# Filter.net
KiCad netlist of a schematic drawn in EAGLE
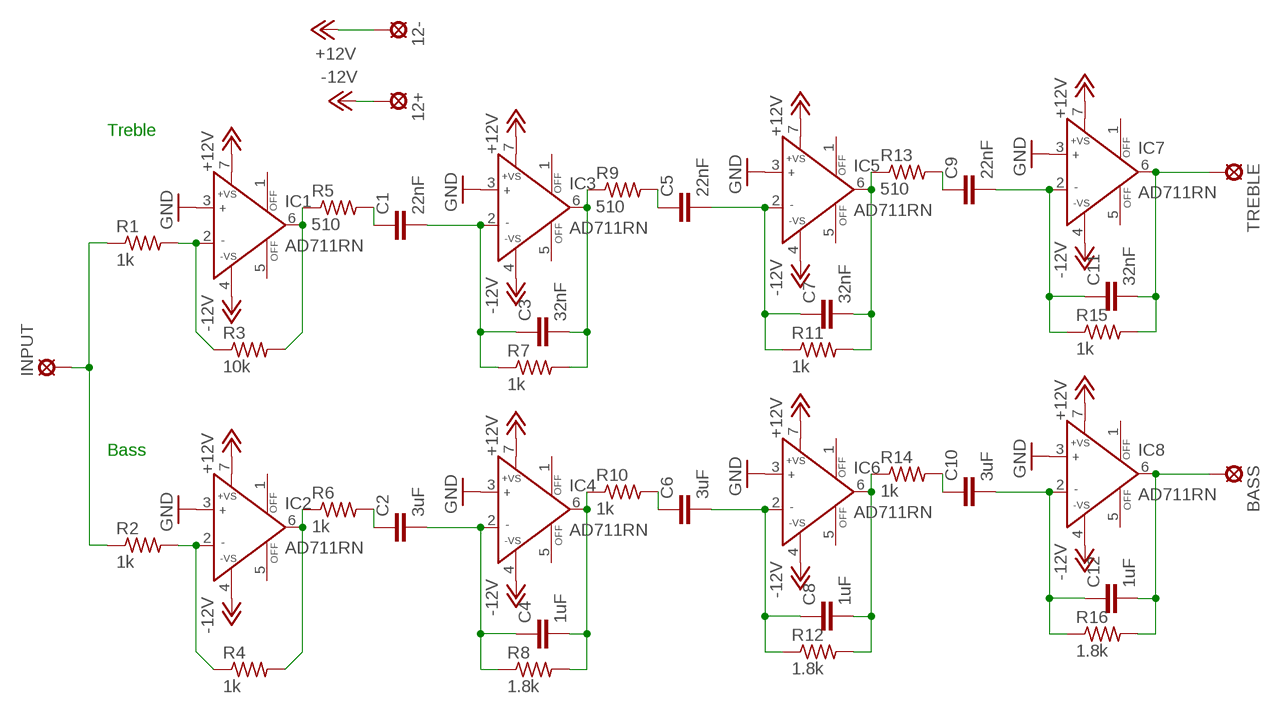
[diagram p0: schematic, sheet 1]

(export (version "E")
  (design (tool "Eeschema 10.0.6"))
  (components
    (comp (ref "12+")
      (value "MCS10B")
      (footprint "eagle-import:MCS10B")
      (libsource (lib "eagle-import") (part "MCS10B"))
    )
    (comp (ref "12-")
      (value "MCS10B")
      (footprint "eagle-import:MCS10B")
      (libsource (lib "eagle-import") (part "MCS10B"))
    )
    (comp (ref "BASS")
      (value "MCS10B")
      (footprint "eagle-import:MCS10B")
      (libsource (lib "eagle-import") (part "MCS10B"))
    )
    (comp (ref "C1")
      (value "22nF")
      (footprint "eagle-import:C0805")
      (fields (field (name "MPN") "UA741CPE4"))
      (libsource (lib "eagle-import") (part "C"))
    )
    (comp (ref "C2")
      (value "3uF")
      (footprint "eagle-import:C0805")
      (fields (field (name "MPN") "TMCP1C335KTRF"))
      (libsource (lib "eagle-import") (part "C"))
    )
    (comp (ref "C3")
      (value "32nF")
      (footprint "eagle-import:C0805")
      (libsource (lib "eagle-import") (part "C"))
    )
    (comp (ref "C4")
      (value "1uF")
      (footprint "eagle-import:C0805")
      (fields (field (name "MPN") "6TPU33MSK"))
      (libsource (lib "eagle-import") (part "C"))
    )
    (comp (ref "C5")
      (value "22nF")
      (footprint "eagle-import:C0805")
      (fields (field (name "MPN") "UA741CPE4"))
      (libsource (lib "eagle-import") (part "C"))
    )
    (comp (ref "C6")
      (value "3uF")
      (footprint "eagle-import:C0805")
      (fields (field (name "MPN") "TMCP1C335KTRF"))
      (libsource (lib "eagle-import") (part "C"))
    )
    (comp (ref "C7")
      (value "32nF")
      (footprint "eagle-import:C0805")
      (libsource (lib "eagle-import") (part "C"))
    )
    (comp (ref "C8")
      (value "1uF")
      (footprint "eagle-import:C0805")
      (fields (field (name "MPN") "6TPU33MSK"))
      (libsource (lib "eagle-import") (part "C"))
    )
    (comp (ref "C9")
      (value "22nF")
      (footprint "eagle-import:C0805")
      (fields (field (name "MPN") "UA741CPE4"))
      (libsource (lib "eagle-import") (part "C"))
    )
    (comp (ref "C10")
      (value "3uF")
      (footprint "eagle-import:C0805")
      (fields (field (name "MPN") "TMCP1C335KTRF"))
      (libsource (lib "eagle-import") (part "C"))
    )
    (comp (ref "C11")
      (value "32nF")
      (footprint "eagle-import:C0805")
      (libsource (lib "eagle-import") (part "C"))
    )
    (comp (ref "C12")
      (value "1uF")
      (footprint "eagle-import:C0805")
      (fields (field (name "MPN") "6TPU33MSK"))
      (libsource (lib "eagle-import") (part "C"))
    )
    (comp (ref "IC1")
      (value "AD711RN")
      (footprint "eagle-import:SO8")
      (fields
        (field (name "MF") "ALTERA CORPORATION")
        (field (name "MPN") "AD711KRZ")
        (field (name "MF_1") "TEXAS INSTRUMENTS")
        (field (name "MPN_1") "UA741CP")
        (field (name "OC_NEWARK") "60K7043")
      )
      (libsource (lib "eagle-import") (part "AD711RN"))
    )
    (comp (ref "IC2")
      (value "AD711RN")
      (footprint "eagle-import:SO8")
      (fields
        (field (name "MF") "ALTERA CORPORATION")
        (field (name "MPN") "AD711KRZ")
        (field (name "MF_1") "TEXAS INSTRUMENTS")
        (field (name "MPN_1") "UA741CP")
        (field (name "OC_NEWARK") "60K7043")
      )
      (libsource (lib "eagle-import") (part "AD711RN"))
    )
    (comp (ref "IC3")
      (value "AD711RN")
      (footprint "eagle-import:SO8")
      (fields
        (field (name "MF") "ALTERA CORPORATION")
        (field (name "MPN") "AD711KRZ")
        (field (name "MF_1") "TEXAS INSTRUMENTS")
        (field (name "MPN_1") "UA741CP")
        (field (name "OC_NEWARK") "60K7043")
      )
      (libsource (lib "eagle-import") (part "AD711RN"))
    )
    (comp (ref "IC4")
      (value "AD711RN")
      (footprint "eagle-import:SO8")
      (fields
        (field (name "MF") "ALTERA CORPORATION")
        (field (name "MPN") "AD711KRZ")
        (field (name "MF_1") "TEXAS INSTRUMENTS")
        (field (name "MPN_1") "UA741CP")
        (field (name "OC_NEWARK") "60K7043")
      )
      (libsource (lib "eagle-import") (part "AD711RN"))
    )
    (comp (ref "IC5")
      (value "AD711RN")
      (footprint "eagle-import:SO8")
      (fields
        (field (name "MF") "ALTERA CORPORATION")
        (field (name "MPN") "AD711KRZ")
        (field (name "MF_1") "TEXAS INSTRUMENTS")
        (field (name "MPN_1") "UA741CP")
        (field (name "OC_NEWARK") "60K7043")
      )
      (libsource (lib "eagle-import") (part "AD711RN"))
    )
    (comp (ref "IC6")
      (value "AD711RN")
      (footprint "eagle-import:SO8")
      (fields
        (field (name "MF") "ALTERA CORPORATION")
        (field (name "MPN") "AD711KRZ")
        (field (name "MF_1") "TEXAS INSTRUMENTS")
        (field (name "MPN_1") "UA741CP")
        (field (name "OC_NEWARK") "60K7043")
      )
      (libsource (lib "eagle-import") (part "AD711RN"))
    )
    (comp (ref "IC7")
      (value "AD711RN")
      (footprint "eagle-import:SO8")
      (fields
        (field (name "MF") "ALTERA CORPORATION")
        (field (name "MPN") "AD711KRZ")
        (field (name "MF_1") "TEXAS INSTRUMENTS")
        (field (name "MPN_1") "UA741CP")
        (field (name "OC_NEWARK") "60K7043")
      )
      (libsource (lib "eagle-import") (part "AD711RN"))
    )
    (comp (ref "IC8")
      (value "AD711RN")
      (footprint "eagle-import:SO8")
      (fields
        (field (name "MF") "ALTERA CORPORATION")
        (field (name "MPN") "AD711KRZ")
        (field (name "MF_1") "TEXAS INSTRUMENTS")
        (field (name "MPN_1") "UA741CP")
        (field (name "OC_NEWARK") "60K7043")
      )
      (libsource (lib "eagle-import") (part "AD711RN"))
    )
    (comp (ref "INPUT")
      (value "MCS10B")
      (footprint "eagle-import:MCS10B")
      (libsource (lib "eagle-import") (part "MCS10B"))
    )
    (comp (ref "R1")
      (value "1k")
      (footprint "eagle-import:R0603")
      (fields (field (name "MPN") "ERJ-3EKF1001V"))
      (libsource (lib "eagle-import") (part "R-US_R0603"))
    )
    (comp (ref "R2")
      (value "1k")
      (footprint "eagle-import:R0603")
      (fields (field (name "MPN") "ERJ-3EKF1001V"))
      (libsource (lib "eagle-import") (part "R-US_R0603"))
    )
    (comp (ref "R3")
      (value "10k")
      (footprint "eagle-import:R0805")
      (fields (field (name "MPN") "MC0603B104K500CT"))
      (libsource (lib "eagle-import") (part "R-US_R0805"))
    )
    (comp (ref "R4")
      (value "1k")
      (footprint "eagle-import:R0603")
      (fields (field (name "MPN") "ERJ-3EKF1001V"))
      (libsource (lib "eagle-import") (part "R-US_R0603"))
    )
    (comp (ref "R5")
      (value "510")
      (footprint "eagle-import:R0805")
      (fields (field (name "MPN") "ERA-6AEB511V"))
      (libsource (lib "eagle-import") (part "R-US_R0805"))
    )
    (comp (ref "R6")
      (value "1k")
      (footprint "eagle-import:R0603")
      (fields (field (name "MPN") "ERJ-3EKF1001V"))
      (libsource (lib "eagle-import") (part "R-US_R0603"))
    )
    (comp (ref "R7")
      (value "1k")
      (footprint "eagle-import:R0603")
      (fields (field (name "MPN") "ERJ-3EKF1001V"))
      (libsource (lib "eagle-import") (part "R-US_R0603"))
    )
    (comp (ref "R8")
      (value "1.8k")
      (footprint "eagle-import:R0805")
      (fields (field (name "MPN") "ERA-6AEB182V"))
      (libsource (lib "eagle-import") (part "R-US_R0805"))
    )
    (comp (ref "R9")
      (value "510")
      (footprint "eagle-import:R0805")
      (fields (field (name "MPN") "ERA-6AEB511V"))
      (libsource (lib "eagle-import") (part "R-US_R0805"))
    )
    (comp (ref "R10")
      (value "1k")
      (footprint "eagle-import:R0603")
      (fields (field (name "MPN") "ERJ-3EKF1001V"))
      (libsource (lib "eagle-import") (part "R-US_R0603"))
    )
    (comp (ref "R11")
      (value "1k")
      (footprint "eagle-import:R0603")
      (fields (field (name "MPN") "ERJ-3EKF1001V"))
      (libsource (lib "eagle-import") (part "R-US_R0603"))
    )
    (comp (ref "R12")
      (value "1.8k")
      (footprint "eagle-import:R0805")
      (fields (field (name "MPN") "ERA-6AEB182V"))
      (libsource (lib "eagle-import") (part "R-US_R0805"))
    )
    (comp (ref "R13")
      (value "510")
      (footprint "eagle-import:R0805")
      (fields (field (name "MPN") "ERA-6AEB511V"))
      (libsource (lib "eagle-import") (part "R-US_R0805"))
    )
    (comp (ref "R14")
      (value "1k")
      (footprint "eagle-import:R0603")
      (fields (field (name "MPN") "ERJ-3EKF1001V"))
      (libsource (lib "eagle-import") (part "R-US_R0603"))
    )
    (comp (ref "R15")
      (value "1k")
      (footprint "eagle-import:R0603")
      (fields (field (name "MPN") "ERJ-3EKF1001V"))
      (libsource (lib "eagle-import") (part "R-US_R0603"))
    )
    (comp (ref "R16")
      (value "1.8k")
      (footprint "eagle-import:R0805")
      (fields (field (name "MPN") "ERA-6AEB182V"))
      (libsource (lib "eagle-import") (part "R-US_R0805"))
    )
    (comp (ref "TREBLE")
      (value "MCS10B")
      (footprint "eagle-import:MCS10B")
      (libsource (lib "eagle-import") (part "MCS10B"))
    )
  )
  (nets
    (net (code "1") (name "+12V") (class "Default")
      (node (ref "12-") (pin "MP") (pinfunction "MP_MP") (pintype "passive"))
      (node (ref "IC1") (pin "7") (pinfunction "+VS_7") (pintype "input"))
      (node (ref "IC2") (pin "7") (pinfunction "+VS_7") (pintype "input"))
      (node (ref "IC3") (pin "7") (pinfunction "+VS_7") (pintype "input"))
      (node (ref "IC4") (pin "7") (pinfunction "+VS_7") (pintype "input"))
      (node (ref "IC5") (pin "7") (pinfunction "+VS_7") (pintype "input"))
      (node (ref "IC6") (pin "7") (pinfunction "+VS_7") (pintype "input"))
      (node (ref "IC7") (pin "7") (pinfunction "+VS_7") (pintype "input"))
      (node (ref "IC8") (pin "7") (pinfunction "+VS_7") (pintype "input"))
    )
    (net (code "2") (name "-12V") (class "Default")
      (node (ref "12+") (pin "MP") (pinfunction "MP_MP") (pintype "passive"))
      (node (ref "IC1") (pin "4") (pinfunction "-VS_4") (pintype "input"))
      (node (ref "IC2") (pin "4") (pinfunction "-VS_4") (pintype "input"))
      (node (ref "IC3") (pin "4") (pinfunction "-VS_4") (pintype "input"))
      (node (ref "IC4") (pin "4") (pinfunction "-VS_4") (pintype "input"))
      (node (ref "IC5") (pin "4") (pinfunction "-VS_4") (pintype "input"))
      (node (ref "IC6") (pin "4") (pinfunction "-VS_4") (pintype "input"))
      (node (ref "IC7") (pin "4") (pinfunction "-VS_4") (pintype "input"))
      (node (ref "IC8") (pin "4") (pinfunction "-VS_4") (pintype "input"))
    )
    (net (code "3") (name "GND") (class "Default")
      (node (ref "IC1") (pin "3") (pinfunction "IN+_3") (pintype "input"))
      (node (ref "IC2") (pin "3") (pinfunction "IN+_3") (pintype "input"))
      (node (ref "IC3") (pin "3") (pinfunction "IN+_3") (pintype "input"))
      (node (ref "IC4") (pin "3") (pinfunction "IN+_3") (pintype "input"))
      (node (ref "IC5") (pin "3") (pinfunction "IN+_3") (pintype "input"))
      (node (ref "IC6") (pin "3") (pinfunction "IN+_3") (pintype "input"))
      (node (ref "IC7") (pin "3") (pinfunction "IN+_3") (pintype "input"))
      (node (ref "IC8") (pin "3") (pinfunction "IN+_3") (pintype "input"))
    )
    (net (code "4") (name "Net-(C1-Pad1)") (class "Default")
      (node (ref "C1") (pin "1") (pinfunction "1_1") (pintype "passive"))
      (node (ref "R5") (pin "2") (pinfunction "2_2") (pintype "passive"))
    )
    (net (code "5") (name "Net-(C2-Pad1)") (class "Default")
      (node (ref "C2") (pin "1") (pinfunction "1_1") (pintype "passive"))
      (node (ref "R6") (pin "2") (pinfunction "2_2") (pintype "passive"))
    )
    (net (code "6") (name "Net-(C5-Pad1)") (class "Default")
      (node (ref "C5") (pin "1") (pinfunction "1_1") (pintype "passive"))
      (node (ref "R9") (pin "2") (pinfunction "2_2") (pintype "passive"))
    )
    (net (code "7") (name "Net-(C6-Pad1)") (class "Default")
      (node (ref "C6") (pin "1") (pinfunction "1_1") (pintype "passive"))
      (node (ref "R10") (pin "2") (pinfunction "2_2") (pintype "passive"))
    )
    (net (code "8") (name "Net-(C9-Pad1)") (class "Default")
      (node (ref "C9") (pin "1") (pinfunction "1_1") (pintype "passive"))
      (node (ref "R13") (pin "2") (pinfunction "2_2") (pintype "passive"))
    )
    (net (code "9") (name "Net-(C10-Pad1)") (class "Default")
      (node (ref "C10") (pin "1") (pinfunction "1_1") (pintype "passive"))
      (node (ref "R14") (pin "2") (pinfunction "2_2") (pintype "passive"))
    )
    (net (code "10") (name "Net-(IC1-IN-)") (class "Default")
      (node (ref "IC1") (pin "2") (pinfunction "IN-_2") (pintype "input"))
      (node (ref "R1") (pin "2") (pinfunction "2_2") (pintype "passive"))
      (node (ref "R3") (pin "1") (pinfunction "1_1") (pintype "passive"))
    )
    (net (code "11") (name "Net-(IC1-OUT)") (class "Default")
      (node (ref "IC1") (pin "6") (pinfunction "OUT_6") (pintype "output"))
      (node (ref "R3") (pin "2") (pinfunction "2_2") (pintype "passive"))
      (node (ref "R5") (pin "1") (pinfunction "1_1") (pintype "passive"))
    )
    (net (code "12") (name "Net-(IC2-IN-)") (class "Default")
      (node (ref "IC2") (pin "2") (pinfunction "IN-_2") (pintype "input"))
      (node (ref "R2") (pin "2") (pinfunction "2_2") (pintype "passive"))
      (node (ref "R4") (pin "1") (pinfunction "1_1") (pintype "passive"))
    )
    (net (code "13") (name "Net-(IC2-OUT)") (class "Default")
      (node (ref "IC2") (pin "6") (pinfunction "OUT_6") (pintype "output"))
      (node (ref "R4") (pin "2") (pinfunction "2_2") (pintype "passive"))
      (node (ref "R6") (pin "1") (pinfunction "1_1") (pintype "passive"))
    )
    (net (code "14") (name "Net-(IC3-IN-)") (class "Default")
      (node (ref "C1") (pin "2") (pinfunction "2_2") (pintype "passive"))
      (node (ref "C3") (pin "1") (pinfunction "1_1") (pintype "passive"))
      (node (ref "IC3") (pin "2") (pinfunction "IN-_2") (pintype "input"))
      (node (ref "R7") (pin "1") (pinfunction "1_1") (pintype "passive"))
    )
    (net (code "15") (name "Net-(IC3-OUT)") (class "Default")
      (node (ref "C3") (pin "2") (pinfunction "2_2") (pintype "passive"))
      (node (ref "IC3") (pin "6") (pinfunction "OUT_6") (pintype "output"))
      (node (ref "R7") (pin "2") (pinfunction "2_2") (pintype "passive"))
      (node (ref "R9") (pin "1") (pinfunction "1_1") (pintype "passive"))
    )
    (net (code "16") (name "Net-(IC4-IN-)") (class "Default")
      (node (ref "C2") (pin "2") (pinfunction "2_2") (pintype "passive"))
      (node (ref "C4") (pin "1") (pinfunction "1_1") (pintype "passive"))
      (node (ref "IC4") (pin "2") (pinfunction "IN-_2") (pintype "input"))
      (node (ref "R8") (pin "1") (pinfunction "1_1") (pintype "passive"))
    )
    (net (code "17") (name "Net-(IC4-OUT)") (class "Default")
      (node (ref "C4") (pin "2") (pinfunction "2_2") (pintype "passive"))
      (node (ref "IC4") (pin "6") (pinfunction "OUT_6") (pintype "output"))
      (node (ref "R10") (pin "1") (pinfunction "1_1") (pintype "passive"))
      (node (ref "R8") (pin "2") (pinfunction "2_2") (pintype "passive"))
    )
    (net (code "18") (name "Net-(IC5-IN-)") (class "Default")
      (node (ref "C5") (pin "2") (pinfunction "2_2") (pintype "passive"))
      (node (ref "C7") (pin "1") (pinfunction "1_1") (pintype "passive"))
      (node (ref "IC5") (pin "2") (pinfunction "IN-_2") (pintype "input"))
      (node (ref "R11") (pin "1") (pinfunction "1_1") (pintype "passive"))
    )
    (net (code "19") (name "Net-(IC5-OUT)") (class "Default")
      (node (ref "C7") (pin "2") (pinfunction "2_2") (pintype "passive"))
      (node (ref "IC5") (pin "6") (pinfunction "OUT_6") (pintype "output"))
      (node (ref "R11") (pin "2") (pinfunction "2_2") (pintype "passive"))
      (node (ref "R13") (pin "1") (pinfunction "1_1") (pintype "passive"))
    )
    (net (code "20") (name "Net-(IC6-IN-)") (class "Default")
      (node (ref "C6") (pin "2") (pinfunction "2_2") (pintype "passive"))
      (node (ref "C8") (pin "1") (pinfunction "1_1") (pintype "passive"))
      (node (ref "IC6") (pin "2") (pinfunction "IN-_2") (pintype "input"))
      (node (ref "R12") (pin "1") (pinfunction "1_1") (pintype "passive"))
    )
    (net (code "21") (name "Net-(IC6-OUT)") (class "Default")
      (node (ref "C8") (pin "2") (pinfunction "2_2") (pintype "passive"))
      (node (ref "IC6") (pin "6") (pinfunction "OUT_6") (pintype "output"))
      (node (ref "R12") (pin "2") (pinfunction "2_2") (pintype "passive"))
      (node (ref "R14") (pin "1") (pinfunction "1_1") (pintype "passive"))
    )
    (net (code "22") (name "Net-(IC7-IN-)") (class "Default")
      (node (ref "C11") (pin "1") (pinfunction "1_1") (pintype "passive"))
      (node (ref "C9") (pin "2") (pinfunction "2_2") (pintype "passive"))
      (node (ref "IC7") (pin "2") (pinfunction "IN-_2") (pintype "input"))
      (node (ref "R15") (pin "1") (pinfunction "1_1") (pintype "passive"))
    )
    (net (code "23") (name "Net-(IC7-OUT)") (class "Default")
      (node (ref "C11") (pin "2") (pinfunction "2_2") (pintype "passive"))
      (node (ref "IC7") (pin "6") (pinfunction "OUT_6") (pintype "output"))
      (node (ref "R15") (pin "2") (pinfunction "2_2") (pintype "passive"))
      (node (ref "TREBLE") (pin "MP") (pinfunction "MP_MP") (pintype "passive"))
    )
    (net (code "24") (name "Net-(IC8-IN-)") (class "Default")
      (node (ref "C10") (pin "2") (pinfunction "2_2") (pintype "passive"))
      (node (ref "C12") (pin "1") (pinfunction "1_1") (pintype "passive"))
      (node (ref "IC8") (pin "2") (pinfunction "IN-_2") (pintype "input"))
      (node (ref "R16") (pin "1") (pinfunction "1_1") (pintype "passive"))
    )
    (net (code "25") (name "Net-(IC8-OUT)") (class "Default")
      (node (ref "BASS") (pin "MP") (pinfunction "MP_MP") (pintype "passive"))
      (node (ref "C12") (pin "2") (pinfunction "2_2") (pintype "passive"))
      (node (ref "IC8") (pin "6") (pinfunction "OUT_6") (pintype "output"))
      (node (ref "R16") (pin "2") (pinfunction "2_2") (pintype "passive"))
    )
    (net (code "26") (name "Net-(INPUT-PadMP)") (class "Default")
      (node (ref "INPUT") (pin "MP") (pinfunction "MP_MP") (pintype "passive"))
      (node (ref "R1") (pin "1") (pinfunction "1_1") (pintype "passive"))
      (node (ref "R2") (pin "1") (pinfunction "1_1") (pintype "passive"))
    )
    (net (code "27") (name "unconnected-(IC1-OFF-Pad1)") (class "Default")
      (node (ref "IC1") (pin "1") (pinfunction "OFF_1") (pintype "passive"))
    )
    (net (code "28") (name "unconnected-(IC1-OFF-Pad5)") (class "Default")
      (node (ref "IC1") (pin "5") (pinfunction "OFF_5") (pintype "passive"))
    )
    (net (code "29") (name "unconnected-(IC2-OFF-Pad1)") (class "Default")
      (node (ref "IC2") (pin "1") (pinfunction "OFF_1") (pintype "passive"))
    )
    (net (code "30") (name "unconnected-(IC2-OFF-Pad5)") (class "Default")
      (node (ref "IC2") (pin "5") (pinfunction "OFF_5") (pintype "passive"))
    )
    (net (code "31") (name "unconnected-(IC3-OFF-Pad1)") (class "Default")
      (node (ref "IC3") (pin "1") (pinfunction "OFF_1") (pintype "passive"))
    )
    (net (code "32") (name "unconnected-(IC3-OFF-Pad5)") (class "Default")
      (node (ref "IC3") (pin "5") (pinfunction "OFF_5") (pintype "passive"))
    )
    (net (code "33") (name "unconnected-(IC4-OFF-Pad1)") (class "Default")
      (node (ref "IC4") (pin "1") (pinfunction "OFF_1") (pintype "passive"))
    )
    (net (code "34") (name "unconnected-(IC4-OFF-Pad5)") (class "Default")
      (node (ref "IC4") (pin "5") (pinfunction "OFF_5") (pintype "passive"))
    )
    (net (code "35") (name "unconnected-(IC5-OFF-Pad1)") (class "Default")
      (node (ref "IC5") (pin "1") (pinfunction "OFF_1") (pintype "passive"))
    )
    (net (code "36") (name "unconnected-(IC5-OFF-Pad5)") (class "Default")
      (node (ref "IC5") (pin "5") (pinfunction "OFF_5") (pintype "passive"))
    )
    (net (code "37") (name "unconnected-(IC6-OFF-Pad1)") (class "Default")
      (node (ref "IC6") (pin "1") (pinfunction "OFF_1") (pintype "passive"))
    )
    (net (code "38") (name "unconnected-(IC6-OFF-Pad5)") (class "Default")
      (node (ref "IC6") (pin "5") (pinfunction "OFF_5") (pintype "passive"))
    )
    (net (code "39") (name "unconnected-(IC7-OFF-Pad1)") (class "Default")
      (node (ref "IC7") (pin "1") (pinfunction "OFF_1") (pintype "passive"))
    )
    (net (code "40") (name "unconnected-(IC7-OFF-Pad5)") (class "Default")
      (node (ref "IC7") (pin "5") (pinfunction "OFF_5") (pintype "passive"))
    )
    (net (code "41") (name "unconnected-(IC8-OFF-Pad1)") (class "Default")
      (node (ref "IC8") (pin "1") (pinfunction "OFF_1") (pintype "passive"))
    )
    (net (code "42") (name "unconnected-(IC8-OFF-Pad5)") (class "Default")
      (node (ref "IC8") (pin "5") (pinfunction "OFF_5") (pintype "passive"))
    )
  )
)
